# Processor_Interface.net
KiCad netlist of a schematic drawn in Altium Designer
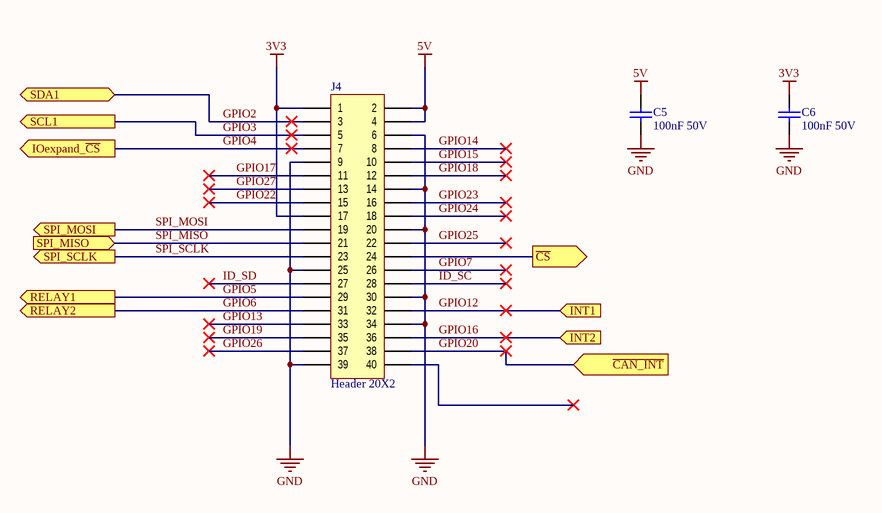
[diagram p0: Processor_Interface.SchDoc]

(export (version "E")
  (design (tool "Eeschema 10.0.6"))
  (components
    (comp (ref "C5")
      (value "100nF 50V")
      (footprint "WCT:0603C_L")
      (fields
        (field (name "MANUFACTURER") "Yageo")
        (field (name "MANUFACTURER PART NUMBER") "CC0603ZRY5V9BB104")
        (field (name "TOLERANCE") "-20%, +80%")
      )
      (libsource (lib "WCT") (part "Cap100nF_50V_0603"))
    )
    (comp (ref "C6")
      (value "100nF 50V")
      (footprint "0603C_L")
      (fields
        (field (name "MANUFACTURER") "Yageo")
        (field (name "MANUFACTURER PART NUMBER") "CC0603ZRY5V9BB104")
        (field (name "TOLERANCE") "-20%, +80%")
      )
      (libsource (lib "WCT") (part "Cap100nF_50V_0603"))
    )
    (comp (ref "J4")
      (value "Header 20X2")
      (footprint "HDR2X20")
      (description "Header, 20-Pin, Dual row")
      (fields (field (name "PUBLISHER") "Altium Limited"))
      (libsource (lib "Miscellaneous Connectors") (part "Header 20X2"))
    )
  )
  (nets
    (net (code "1") (name "/GPIO2") (class "Default")
      (node (ref "J4") (pin "3") (pinfunction "3_3") (pintype "passive"))
    )
    (net (code "2") (name "/GPIO3") (class "Default")
      (node (ref "J4") (pin "5") (pinfunction "5_5") (pintype "passive"))
    )
    (net (code "3") (name "/GPIO4") (class "Default")
      (node (ref "J4") (pin "7") (pinfunction "7_7") (pintype "passive"))
    )
    (net (code "4") (name "/GPIO5") (class "Default")
      (node (ref "J4") (pin "29") (pinfunction "29_29") (pintype "passive"))
    )
    (net (code "5") (name "/GPIO6") (class "Default")
      (node (ref "J4") (pin "31") (pinfunction "31_31") (pintype "passive"))
    )
    (net (code "6") (name "/GPIO7") (class "Default")
      (node (ref "J4") (pin "26") (pinfunction "26_26") (pintype "passive+no_connect"))
    )
    (net (code "7") (name "/GPIO12") (class "Default")
      (node (ref "J4") (pin "32") (pinfunction "32_32") (pintype "passive"))
    )
    (net (code "8") (name "/GPIO13") (class "Default")
      (node (ref "J4") (pin "33") (pinfunction "33_33") (pintype "passive+no_connect"))
    )
    (net (code "9") (name "/GPIO14") (class "Default")
      (node (ref "J4") (pin "8") (pinfunction "8_8") (pintype "passive+no_connect"))
    )
    (net (code "10") (name "/GPIO15") (class "Default")
      (node (ref "J4") (pin "10") (pinfunction "10_10") (pintype "passive+no_connect"))
    )
    (net (code "11") (name "/GPIO16") (class "Default")
      (node (ref "J4") (pin "36") (pinfunction "36_36") (pintype "passive"))
    )
    (net (code "12") (name "/GPIO17") (class "Default")
      (node (ref "J4") (pin "11") (pinfunction "11_11") (pintype "passive+no_connect"))
    )
    (net (code "13") (name "/GPIO18") (class "Default")
      (node (ref "J4") (pin "12") (pinfunction "12_12") (pintype "passive+no_connect"))
    )
    (net (code "14") (name "/GPIO19") (class "Default")
      (node (ref "J4") (pin "35") (pinfunction "35_35") (pintype "passive+no_connect"))
    )
    (net (code "15") (name "/GPIO20") (class "Default")
      (node (ref "J4") (pin "38") (pinfunction "38_38") (pintype "passive+no_connect"))
    )
    (net (code "16") (name "/GPIO22") (class "Default")
      (node (ref "J4") (pin "15") (pinfunction "15_15") (pintype "passive+no_connect"))
    )
    (net (code "17") (name "/GPIO23") (class "Default")
      (node (ref "J4") (pin "16") (pinfunction "16_16") (pintype "passive+no_connect"))
    )
    (net (code "18") (name "/GPIO24") (class "Default")
      (node (ref "J4") (pin "18") (pinfunction "18_18") (pintype "passive+no_connect"))
    )
    (net (code "19") (name "/GPIO25") (class "Default")
      (node (ref "J4") (pin "22") (pinfunction "22_22") (pintype "passive+no_connect"))
    )
    (net (code "20") (name "/GPIO26") (class "Default")
      (node (ref "J4") (pin "37") (pinfunction "37_37") (pintype "passive+no_connect"))
    )
    (net (code "21") (name "/GPIO27") (class "Default")
      (node (ref "J4") (pin "13") (pinfunction "13_13") (pintype "passive+no_connect"))
    )
    (net (code "22") (name "/ID_SC") (class "Default")
      (node (ref "J4") (pin "28") (pinfunction "28_28") (pintype "passive+no_connect"))
    )
    (net (code "23") (name "/ID_SD") (class "Default")
      (node (ref "J4") (pin "27") (pinfunction "27_27") (pintype "passive+no_connect"))
    )
    (net (code "24") (name "/SPI_MISO") (class "Default")
      (node (ref "J4") (pin "21") (pinfunction "21_21") (pintype "passive"))
    )
    (net (code "25") (name "/SPI_MOSI") (class "Default")
      (node (ref "J4") (pin "19") (pinfunction "19_19") (pintype "passive"))
    )
    (net (code "26") (name "/SPI_SCLK") (class "Default")
      (node (ref "J4") (pin "23") (pinfunction "23_23") (pintype "passive"))
    )
    (net (code "27") (name "/~{CS}") (class "Default")
      (node (ref "J4") (pin "24") (pinfunction "24_24") (pintype "passive"))
    )
    (net (code "28") (name "3V3") (class "Default")
      (node (ref "C6") (pin "2") (pinfunction "2_2") (pintype "passive"))
      (node (ref "J4") (pin "1") (pinfunction "1_1") (pintype "passive"))
      (node (ref "J4") (pin "17") (pinfunction "17_17") (pintype "passive"))
    )
    (net (code "29") (name "5V") (class "Default")
      (node (ref "C5") (pin "2") (pinfunction "2_2") (pintype "passive"))
      (node (ref "J4") (pin "2") (pinfunction "2_2") (pintype "passive"))
      (node (ref "J4") (pin "4") (pinfunction "4_4") (pintype "passive"))
    )
    (net (code "30") (name "GND") (class "Default")
      (node (ref "C5") (pin "1") (pinfunction "1_1") (pintype "passive"))
      (node (ref "C6") (pin "1") (pinfunction "1_1") (pintype "passive"))
      (node (ref "J4") (pin "14") (pinfunction "14_14") (pintype "passive"))
      (node (ref "J4") (pin "20") (pinfunction "20_20") (pintype "passive"))
      (node (ref "J4") (pin "25") (pinfunction "25_25") (pintype "passive"))
      (node (ref "J4") (pin "30") (pinfunction "30_30") (pintype "passive"))
      (node (ref "J4") (pin "34") (pinfunction "34_34") (pintype "passive"))
      (node (ref "J4") (pin "39") (pinfunction "39_39") (pintype "passive"))
      (node (ref "J4") (pin "6") (pinfunction "6_6") (pintype "passive"))
      (node (ref "J4") (pin "9") (pinfunction "9_9") (pintype "passive"))
    )
    (net (code "31") (name "unconnected-(J4-Pad40)") (class "Default")
      (node (ref "J4") (pin "40") (pinfunction "40_40") (pintype "passive+no_connect"))
    )
  )
)
